# Controller.net
KiCad netlist of a schematic drawn in EAGLE
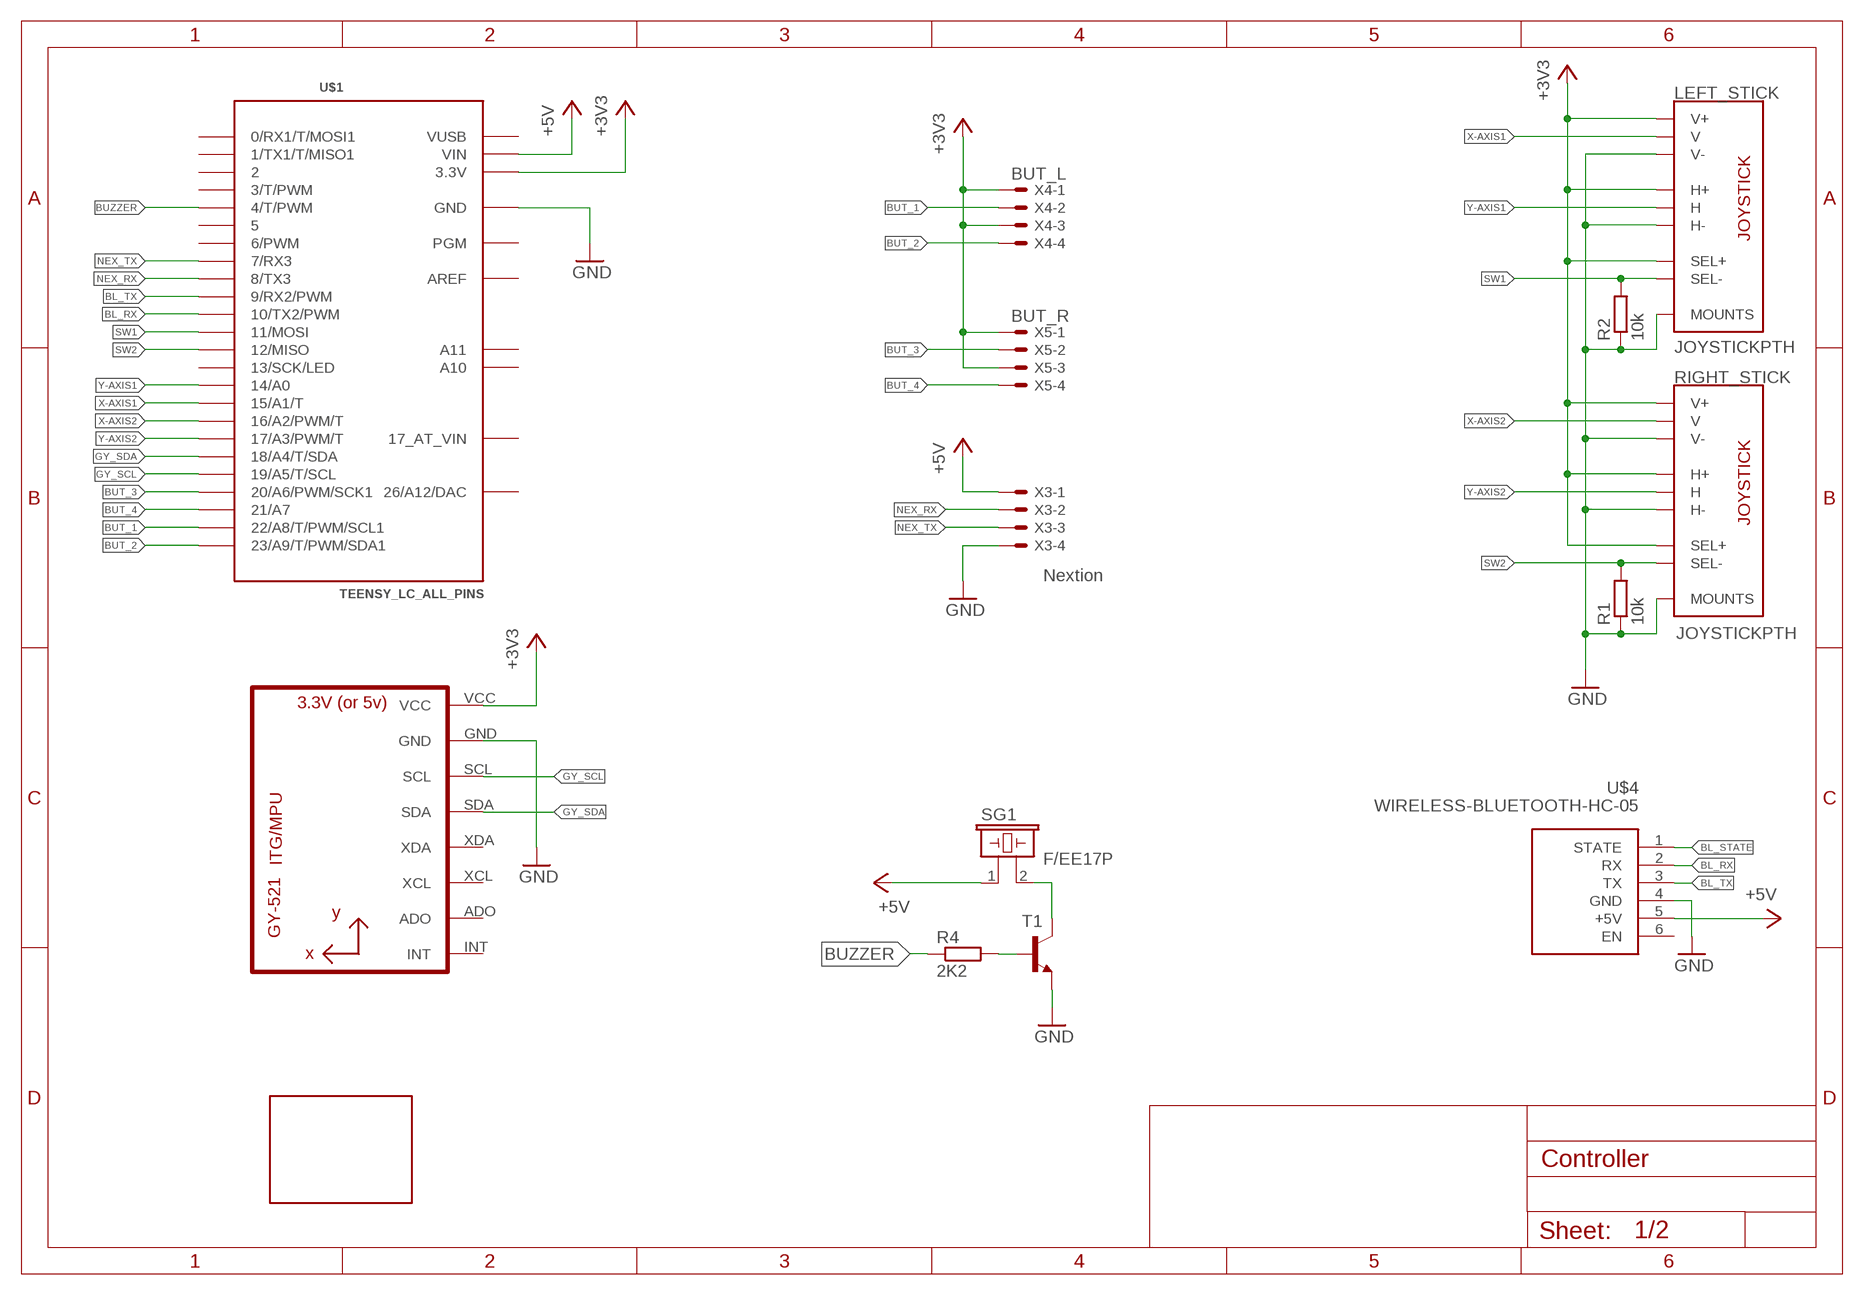
[diagram p0: schematic, sheet 1]
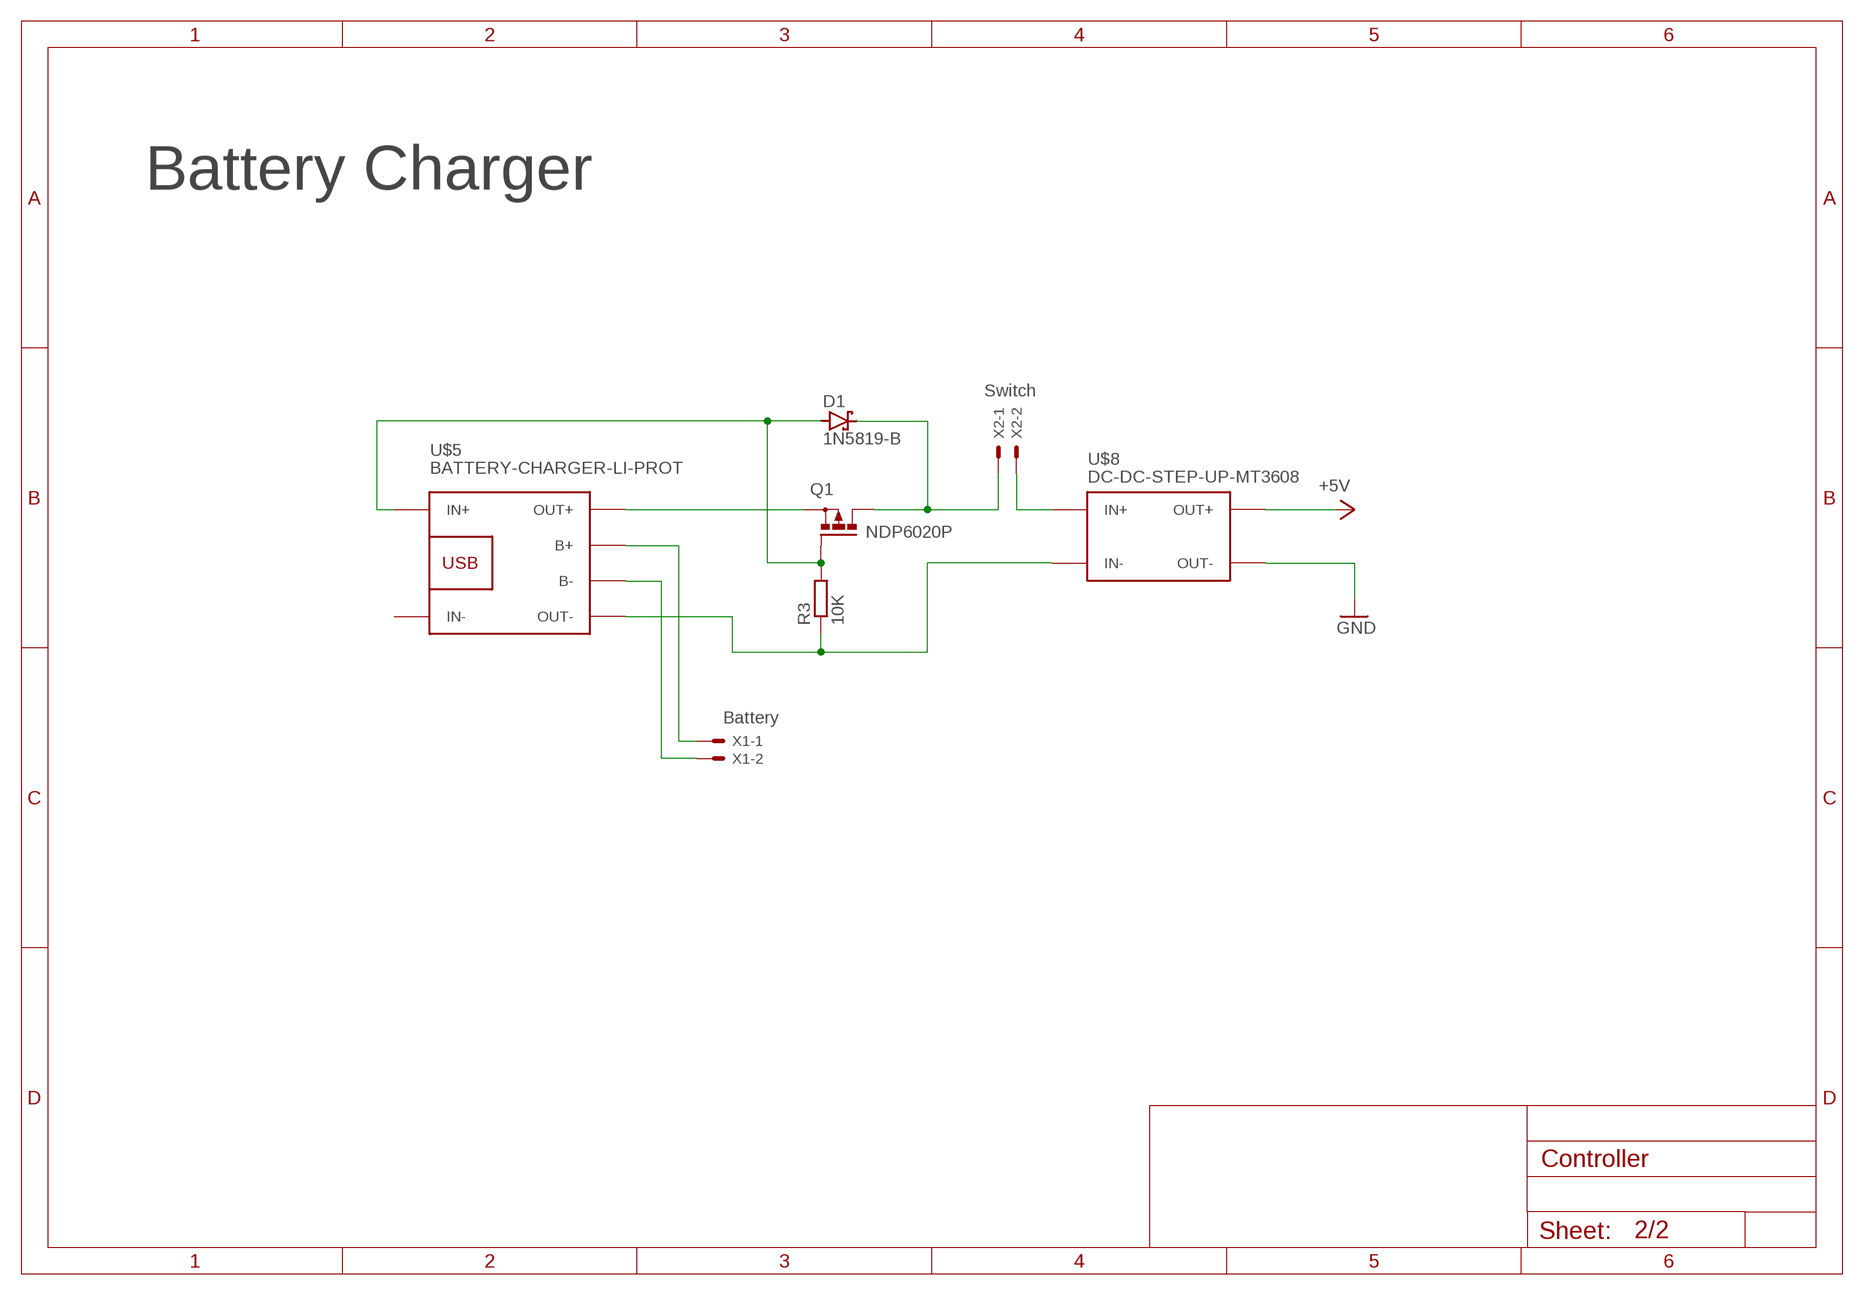
[diagram p1: schematic, sheet 2]

(export (version "E")
  (design (tool "Eeschema 10.0.6"))
  (components
    (comp (ref "LEFT_STICK")
      (value "JOYSTICKPTH")
      (footprint "eagle-import:JOYSTICK")
      (fields (field (name "SPICEPREFIX") "X"))
      (libsource (lib "eagle-import") (part "JOYSTICKPTH"))
    )
    (comp (ref "R1")
      (value "10k")
      (footprint "eagle-import:0207_10")
      (libsource (lib "eagle-import") (part "R-EU_0207/10"))
    )
    (comp (ref "R2")
      (value "10k")
      (footprint "eagle-import:0207_10")
      (libsource (lib "eagle-import") (part "R-EU_0207/10"))
    )
    (comp (ref "R4")
      (value "2K2")
      (footprint "eagle-import:0207_10")
      (libsource (lib "eagle-import") (part "R-EU_0207/10"))
    )
    (comp (ref "RIGHT_STICK")
      (value "JOYSTICKPTH")
      (footprint "eagle-import:JOYSTICK")
      (fields (field (name "SPICEPREFIX") "X"))
      (libsource (lib "eagle-import") (part "JOYSTICKPTH"))
    )
    (comp (ref "SG1")
      (value "F/EE17P")
      (footprint "eagle-import:F_EE17P")
      (libsource (lib "eagle-import") (part "F/EE17P"))
    )
    (comp (ref "T1")
      (value "-NPN-TO92-EBC")
      (footprint "eagle-import:TO92-EBC")
      (libsource (lib "eagle-import") (part "-NPN-TO92-EBC"))
    )
    (comp (ref "U$1")
      (value "TEENSY_LC_ALL_PINS")
      (footprint "eagle-import:TEENSY_3.0-3.2&LC_ALL_PINS")
      (libsource (lib "eagle-import") (part "TEENSY_LC_ALL_PINS"))
    )
    (comp (ref "U$4")
      (value "WIRELESS-BLUETOOTH-HC-05")
      (footprint "eagle-import:WIRELESS-BLUETOOTH-HC-05")
      (libsource (lib "eagle-import") (part "WIRELESS-BLUETOOTH-HC-05"))
    )
    (comp (ref "U$9")
      (value "NX4832K035")
      (footprint "eagle-import:NX4832K035")
      (libsource (lib "eagle-import") (part "NX4832K035"))
    )
    (comp (ref "U1")
      (value "GY-521MPU6050")
      (footprint "eagle-import:GY-521")
      (libsource (lib "eagle-import") (part "GY-521MPU6050"))
    )
    (comp (ref "X3")
      (value "Nextion")
      (footprint "eagle-import:JST-XH-04-PACKAGE-LONG-PAD")
      (libsource (lib "eagle-import") (part "JST-XH-04-PIN-LONG-PAD"))
    )
    (comp (ref "X4")
      (value "BUT_L")
      (footprint "eagle-import:JST-XH-04-PACKAGE-LONG-PAD")
      (libsource (lib "eagle-import") (part "JST-XH-04-PIN-LONG-PAD"))
    )
    (comp (ref "X5")
      (value "BUT_R")
      (footprint "eagle-import:JST-XH-04-PACKAGE-LONG-PAD")
      (libsource (lib "eagle-import") (part "JST-XH-04-PIN-LONG-PAD"))
    )
    (comp (ref "D1")
      (value "1N5819-B")
      (footprint "eagle-import:DO41-7.6")
      (libsource (lib "eagle-import") (part "1N5819-B"))
    )
    (comp (ref "Q1")
      (value "NDP6020P")
      (footprint "eagle-import:TO220BH")
      (libsource (lib "eagle-import") (part "PMOSFET_PTO220BH"))
    )
    (comp (ref "R3")
      (value "10K")
      (footprint "eagle-import:0207_10")
      (libsource (lib "eagle-import") (part "R-EU_0207/10"))
    )
    (comp (ref "U$5")
      (value "BATTERY-CHARGER-LI-PROT")
      (footprint "eagle-import:BATTERY-CHARGER-LI-PROT")
      (libsource (lib "eagle-import") (part "BATTERY-CHARGER-LI-PROT"))
    )
    (comp (ref "U$8")
      (value "DC-DC-STEP-UP-MT3608")
      (footprint "eagle-import:DC-DC-STEP-UP-MT3608")
      (libsource (lib "eagle-import") (part "DC-DC-STEP-UP-MT3608"))
    )
    (comp (ref "X1")
      (value "Battery")
      (footprint "eagle-import:JST-XH-02-PACKAGE-LONG-PAD")
      (libsource (lib "eagle-import") (part "JST-XH-02-PIN-LONG-PAD"))
    )
    (comp (ref "X2")
      (value "Switch")
      (footprint "eagle-import:JST-XH-02-PACKAGE-LONG-PAD")
      (libsource (lib "eagle-import") (part "JST-XH-02-PIN-LONG-PAD"))
    )
  )
  (nets
    (net (code "1") (name "+3V3") (class "Default")
      (node (ref "LEFT_STICK") (pin "B1A") (pinfunction "SEL+_B1A") (pintype "bidirectional"))
      (node (ref "LEFT_STICK") (pin "B1B") (pinfunction "SEL+_B1B") (pintype "bidirectional"))
      (node (ref "LEFT_STICK") (pin "H1") (pinfunction "H+_H1") (pintype "bidirectional"))
      (node (ref "LEFT_STICK") (pin "V1") (pinfunction "V+_V1") (pintype "bidirectional"))
      (node (ref "RIGHT_STICK") (pin "B1A") (pinfunction "SEL+_B1A") (pintype "bidirectional"))
      (node (ref "RIGHT_STICK") (pin "B1B") (pinfunction "SEL+_B1B") (pintype "bidirectional"))
      (node (ref "RIGHT_STICK") (pin "H1") (pinfunction "H+_H1") (pintype "bidirectional"))
      (node (ref "RIGHT_STICK") (pin "V1") (pinfunction "V+_V1") (pintype "bidirectional"))
      (node (ref "U$1") (pin "3.3V") (pinfunction "3.3V_3.3V") (pintype "power_in"))
      (node (ref "U$1") (pin "3.3V1") (pinfunction "3.3V_3.3V1") (pintype "power_in"))
      (node (ref "U1") (pin "VCC") (pinfunction "VCC_VCC") (pintype "bidirectional"))
      (node (ref "X4") (pin "1") (pinfunction "S_1") (pintype "passive"))
      (node (ref "X4") (pin "3") (pinfunction "S_3") (pintype "passive"))
      (node (ref "X5") (pin "1") (pinfunction "S_1") (pintype "passive"))
      (node (ref "X5") (pin "3") (pinfunction "S_3") (pintype "passive"))
    )
    (net (code "2") (name "+5V") (class "Default")
      (node (ref "SG1") (pin "1") (pinfunction "1_1") (pintype "passive"))
      (node (ref "U$1") (pin "VIN") (pinfunction "VIN_VIN") (pintype "power_in"))
      (node (ref "U$4") (pin "5") (pinfunction "+5V_5") (pintype "power_in"))
      (node (ref "U$8") (pin "OUT+") (pinfunction "OUT+_OUT+") (pintype "bidirectional"))
      (node (ref "X3") (pin "1") (pinfunction "S_1") (pintype "passive"))
    )
    (net (code "3") (name "26{slash}A12{slash}DAC") (class "Default")
      (node (ref "U$1") (pin "RESET/DAC") (pinfunction "26/A12/DAC_RESET/DAC") (pintype "power_in"))
    )
    (net (code "4") (name "AREF") (class "Default")
      (node (ref "U$1") (pin "AREF") (pinfunction "AREF_AREF") (pintype "power_in"))
    )
    (net (code "5") (name "BL_RX") (class "Default")
      (node (ref "U$1") (pin "10") (pinfunction "10/TX2/PWM_10") (pintype "bidirectional"))
      (node (ref "U$4") (pin "2") (pinfunction "RX_2") (pintype "bidirectional"))
    )
    (net (code "6") (name "BL_STATE") (class "Default")
      (node (ref "U$4") (pin "1") (pinfunction "STATE_1") (pintype "bidirectional"))
    )
    (net (code "7") (name "BL_TX") (class "Default")
      (node (ref "U$1") (pin "9") (pinfunction "9/RX2/PWM_9") (pintype "bidirectional"))
      (node (ref "U$4") (pin "3") (pinfunction "TX_3") (pintype "bidirectional"))
    )
    (net (code "8") (name "BUT_1") (class "Default")
      (node (ref "U$1") (pin "22/A8") (pinfunction "22/A8/T/PWM/SCL1_22/A8") (pintype "bidirectional"))
      (node (ref "X4") (pin "2") (pinfunction "S_2") (pintype "passive"))
    )
    (net (code "9") (name "BUT_2") (class "Default")
      (node (ref "U$1") (pin "23/A9") (pinfunction "23/A9/T/PWM/SDA1_23/A9") (pintype "bidirectional"))
      (node (ref "X4") (pin "4") (pinfunction "S_4") (pintype "passive"))
    )
    (net (code "10") (name "BUT_3") (class "Default")
      (node (ref "U$1") (pin "20/A6") (pinfunction "20/A6/PWM/SCK1_20/A6") (pintype "bidirectional"))
      (node (ref "X5") (pin "2") (pinfunction "S_2") (pintype "passive"))
    )
    (net (code "11") (name "BUT_4") (class "Default")
      (node (ref "U$1") (pin "21/A7") (pinfunction "21/A7_21/A7") (pintype "bidirectional"))
      (node (ref "X5") (pin "4") (pinfunction "S_4") (pintype "passive"))
    )
    (net (code "12") (name "BUZZER") (class "Default")
      (node (ref "R4") (pin "1") (pinfunction "1_1") (pintype "passive"))
      (node (ref "U$1") (pin "4") (pinfunction "4/T/PWM_4") (pintype "bidirectional"))
    )
    (net (code "13") (name "GND") (class "Default")
      (node (ref "LEFT_STICK") (pin "H3") (pinfunction "H-_H3") (pintype "bidirectional"))
      (node (ref "LEFT_STICK") (pin "MOUNT1") (pinfunction "MOUNTS_MOUNT1") (pintype "bidirectional"))
      (node (ref "LEFT_STICK") (pin "MOUNT2") (pinfunction "MOUNTS_MOUNT2") (pintype "bidirectional"))
      (node (ref "LEFT_STICK") (pin "MOUNT3") (pinfunction "MOUNTS_MOUNT3") (pintype "bidirectional"))
      (node (ref "LEFT_STICK") (pin "MOUNT4") (pinfunction "MOUNTS_MOUNT4") (pintype "bidirectional"))
      (node (ref "LEFT_STICK") (pin "V3") (pinfunction "V-_V3") (pintype "bidirectional"))
      (node (ref "R1") (pin "1") (pinfunction "1_1") (pintype "passive"))
      (node (ref "R2") (pin "1") (pinfunction "1_1") (pintype "passive"))
      (node (ref "RIGHT_STICK") (pin "H3") (pinfunction "H-_H3") (pintype "bidirectional"))
      (node (ref "RIGHT_STICK") (pin "MOUNT1") (pinfunction "MOUNTS_MOUNT1") (pintype "bidirectional"))
      (node (ref "RIGHT_STICK") (pin "MOUNT2") (pinfunction "MOUNTS_MOUNT2") (pintype "bidirectional"))
      (node (ref "RIGHT_STICK") (pin "MOUNT3") (pinfunction "MOUNTS_MOUNT3") (pintype "bidirectional"))
      (node (ref "RIGHT_STICK") (pin "MOUNT4") (pinfunction "MOUNTS_MOUNT4") (pintype "bidirectional"))
      (node (ref "RIGHT_STICK") (pin "V3") (pinfunction "V-_V3") (pintype "bidirectional"))
      (node (ref "T1") (pin "E") (pinfunction "E_E") (pintype "passive"))
      (node (ref "U$1") (pin "AGND") (pinfunction "GND_AGND") (pintype "power_in"))
      (node (ref "U$1") (pin "GND") (pinfunction "GND_GND") (pintype "power_in"))
      (node (ref "U$1") (pin "GND1") (pinfunction "GND_GND1") (pintype "power_in"))
      (node (ref "U$4") (pin "4") (pinfunction "GND_4") (pintype "power_in"))
      (node (ref "U$8") (pin "OUT-") (pinfunction "OUT-_OUT-") (pintype "bidirectional"))
      (node (ref "U1") (pin "GND") (pinfunction "GND_GND") (pintype "bidirectional"))
      (node (ref "X3") (pin "4") (pinfunction "S_4") (pintype "passive"))
    )
    (net (code "14") (name "GY_SCL") (class "Default")
      (node (ref "U$1") (pin "19/A5") (pinfunction "19/A5/T/SCL_19/A5") (pintype "bidirectional"))
      (node (ref "U1") (pin "SCL") (pinfunction "SCL_SCL") (pintype "bidirectional"))
    )
    (net (code "15") (name "GY_SDA") (class "Default")
      (node (ref "U$1") (pin "18/A4") (pinfunction "18/A4/T/SDA_18/A4") (pintype "bidirectional"))
      (node (ref "U1") (pin "SDA") (pinfunction "SDA_SDA") (pintype "bidirectional"))
    )
    (net (code "16") (name "NEX_RX") (class "Default")
      (node (ref "U$1") (pin "8") (pinfunction "8/TX3_8") (pintype "bidirectional"))
      (node (ref "X3") (pin "2") (pinfunction "S_2") (pintype "passive"))
    )
    (net (code "17") (name "NEX_TX") (class "Default")
      (node (ref "U$1") (pin "7") (pinfunction "7/RX3_7") (pintype "bidirectional"))
      (node (ref "X3") (pin "3") (pinfunction "S_3") (pintype "passive"))
    )
    (net (code "18") (name "Net-(D1-PadA)") (class "Default")
      (node (ref "D1") (pin "A") (pinfunction "A_A") (pintype "passive"))
      (node (ref "Q1") (pin "G") (pinfunction "G_G") (pintype "passive"))
      (node (ref "R3") (pin "2") (pinfunction "2_2") (pintype "passive"))
      (node (ref "U$5") (pin "IN+") (pinfunction "IN+_IN+") (pintype "bidirectional"))
    )
    (net (code "19") (name "Net-(Q1-PadS)") (class "Default")
      (node (ref "Q1") (pin "S") (pinfunction "S_S") (pintype "passive"))
      (node (ref "U$5") (pin "OUT+") (pinfunction "OUT+_OUT+") (pintype "bidirectional"))
    )
    (net (code "20") (name "Net-(R3-Pad1)") (class "Default")
      (node (ref "R3") (pin "1") (pinfunction "1_1") (pintype "passive"))
      (node (ref "U$5") (pin "OUT-") (pinfunction "OUT-_OUT-") (pintype "bidirectional"))
      (node (ref "U$8") (pin "IN-") (pinfunction "IN-_IN-") (pintype "bidirectional"))
    )
    (net (code "21") (name "Net-(R4-Pad2)") (class "Default")
      (node (ref "R4") (pin "2") (pinfunction "2_2") (pintype "passive"))
      (node (ref "T1") (pin "B") (pinfunction "B_B") (pintype "passive"))
    )
    (net (code "22") (name "Net-(SG1-Pad2)") (class "Default")
      (node (ref "SG1") (pin "2") (pinfunction "2_2") (pintype "passive"))
      (node (ref "T1") (pin "C") (pinfunction "C_C") (pintype "passive"))
    )
    (net (code "23") (name "Net-(X1A-S)") (class "Default")
      (node (ref "U$5") (pin "B+") (pinfunction "B+_B+") (pintype "bidirectional"))
      (node (ref "X1") (pin "1") (pinfunction "S_1") (pintype "passive"))
    )
    (net (code "24") (name "Net-(X1B-S)") (class "Default")
      (node (ref "U$5") (pin "B-") (pinfunction "B-_B-") (pintype "bidirectional"))
      (node (ref "X1") (pin "2") (pinfunction "S_2") (pintype "passive"))
    )
    (net (code "25") (name "Net-(X2A-S)") (class "Default")
      (node (ref "D1") (pin "C") (pinfunction "C_C") (pintype "passive"))
      (node (ref "Q1") (pin "D") (pinfunction "D_D") (pintype "passive"))
      (node (ref "X2") (pin "1") (pinfunction "S_1") (pintype "passive"))
    )
    (net (code "26") (name "Net-(X2B-S)") (class "Default")
      (node (ref "U$8") (pin "IN+") (pinfunction "IN+_IN+") (pintype "bidirectional"))
      (node (ref "X2") (pin "2") (pinfunction "S_2") (pintype "passive"))
    )
    (net (code "27") (name "SW1") (class "Default")
      (node (ref "LEFT_STICK") (pin "B2A") (pinfunction "SEL-_B2A") (pintype "bidirectional"))
      (node (ref "LEFT_STICK") (pin "B2B") (pinfunction "SEL-_B2B") (pintype "bidirectional"))
      (node (ref "R2") (pin "2") (pinfunction "2_2") (pintype "passive"))
      (node (ref "U$1") (pin "11") (pinfunction "11/MOSI_11") (pintype "bidirectional"))
    )
    (net (code "28") (name "SW2") (class "Default")
      (node (ref "R1") (pin "2") (pinfunction "2_2") (pintype "passive"))
      (node (ref "RIGHT_STICK") (pin "B2A") (pinfunction "SEL-_B2A") (pintype "bidirectional"))
      (node (ref "RIGHT_STICK") (pin "B2B") (pinfunction "SEL-_B2B") (pintype "bidirectional"))
      (node (ref "U$1") (pin "12") (pinfunction "12/MISO_12") (pintype "bidirectional"))
    )
    (net (code "29") (name "VUSB") (class "Default")
      (node (ref "U$1") (pin "VUSB") (pinfunction "VUSB_VUSB") (pintype "power_in"))
    )
    (net (code "30") (name "X-AXIS1") (class "Default")
      (node (ref "LEFT_STICK") (pin "V2") (pinfunction "V_V2") (pintype "bidirectional"))
      (node (ref "U$1") (pin "15/A1") (pinfunction "15/A1/T_15/A1") (pintype "bidirectional"))
    )
    (net (code "31") (name "X-AXIS2") (class "Default")
      (node (ref "RIGHT_STICK") (pin "V2") (pinfunction "V_V2") (pintype "bidirectional"))
      (node (ref "U$1") (pin "16/A2") (pinfunction "16/A2/PWM/T_16/A2") (pintype "bidirectional"))
    )
    (net (code "32") (name "Y-AXIS1") (class "Default")
      (node (ref "LEFT_STICK") (pin "H2") (pinfunction "H_H2") (pintype "bidirectional"))
      (node (ref "U$1") (pin "14/A0") (pinfunction "14/A0_14/A0") (pintype "bidirectional"))
    )
    (net (code "33") (name "Y-AXIS2") (class "Default")
      (node (ref "RIGHT_STICK") (pin "H2") (pinfunction "H_H2") (pintype "bidirectional"))
      (node (ref "U$1") (pin "17/A3") (pinfunction "17/A3/PWM/T_17/A3") (pintype "bidirectional"))
    )
    (net (code "34") (name "unconnected-(U$1-0{slash}RX1{slash}T{slash}MOSI1-Pad0)") (class "Default")
      (node (ref "U$1") (pin "0") (pinfunction "0/RX1/T/MOSI1_0") (pintype "bidirectional"))
    )
    (net (code "35") (name "unconnected-(U$1-1{slash}TX1{slash}T{slash}MISO1-Pad1)") (class "Default")
      (node (ref "U$1") (pin "1") (pinfunction "1/TX1/T/MISO1_1") (pintype "bidirectional"))
    )
    (net (code "36") (name "unconnected-(U$1-3{slash}T{slash}PWM-Pad3)") (class "Default")
      (node (ref "U$1") (pin "3") (pinfunction "3/T/PWM_3") (pintype "bidirectional"))
    )
    (net (code "37") (name "unconnected-(U$1-6{slash}PWM-Pad6)") (class "Default")
      (node (ref "U$1") (pin "6") (pinfunction "6/PWM_6") (pintype "bidirectional"))
    )
    (net (code "38") (name "unconnected-(U$1-13{slash}SCK{slash}LED-Pad13)") (class "Default")
      (node (ref "U$1") (pin "13") (pinfunction "13/SCK/LED_13") (pintype "bidirectional"))
    )
    (net (code "39") (name "unconnected-(U$1-17_AT_VIN-PadVBAT)") (class "Default")
      (node (ref "U$1") (pin "VBAT") (pinfunction "17_AT_VIN_VBAT") (pintype "bidirectional"))
    )
    (net (code "40") (name "unconnected-(U$1-Pad2)") (class "Default")
      (node (ref "U$1") (pin "2") (pinfunction "2_2") (pintype "bidirectional"))
    )
    (net (code "41") (name "unconnected-(U$1-Pad5)") (class "Default")
      (node (ref "U$1") (pin "5") (pinfunction "5_5") (pintype "bidirectional"))
    )
    (net (code "42") (name "unconnected-(U$1-PadA10)") (class "Default")
      (node (ref "U$1") (pin "A10") (pinfunction "A10_A10") (pintype "bidirectional"))
    )
    (net (code "43") (name "unconnected-(U$1-PadA11)") (class "Default")
      (node (ref "U$1") (pin "A11") (pinfunction "A11_A11") (pintype "bidirectional"))
    )
    (net (code "44") (name "unconnected-(U$1-PadPGM)") (class "Default")
      (node (ref "U$1") (pin "PGM") (pinfunction "PGM_PGM") (pintype "bidirectional"))
    )
    (net (code "45") (name "unconnected-(U$4-EN-Pad6)") (class "Default")
      (node (ref "U$4") (pin "6") (pinfunction "EN_6") (pintype "bidirectional"))
    )
    (net (code "46") (name "unconnected-(U$5-PadIN-)") (class "Default")
      (node (ref "U$5") (pin "IN-") (pinfunction "IN-_IN-") (pintype "bidirectional"))
    )
    (net (code "47") (name "unconnected-(U1-PadADO)") (class "Default")
      (node (ref "U1") (pin "ADO") (pinfunction "ADO_ADO") (pintype "bidirectional"))
    )
    (net (code "48") (name "unconnected-(U1-PadINT)") (class "Default")
      (node (ref "U1") (pin "INT") (pinfunction "INT_INT") (pintype "bidirectional"))
    )
    (net (code "49") (name "unconnected-(U1-PadXCL)") (class "Default")
      (node (ref "U1") (pin "XCL") (pinfunction "XCL_XCL") (pintype "bidirectional"))
    )
    (net (code "50") (name "unconnected-(U1-PadXDA)") (class "Default")
      (node (ref "U1") (pin "XDA") (pinfunction "XDA_XDA") (pintype "bidirectional"))
    )
  )
)
